# S7_Power.net
KiCad netlist of a schematic drawn in Altium Designer
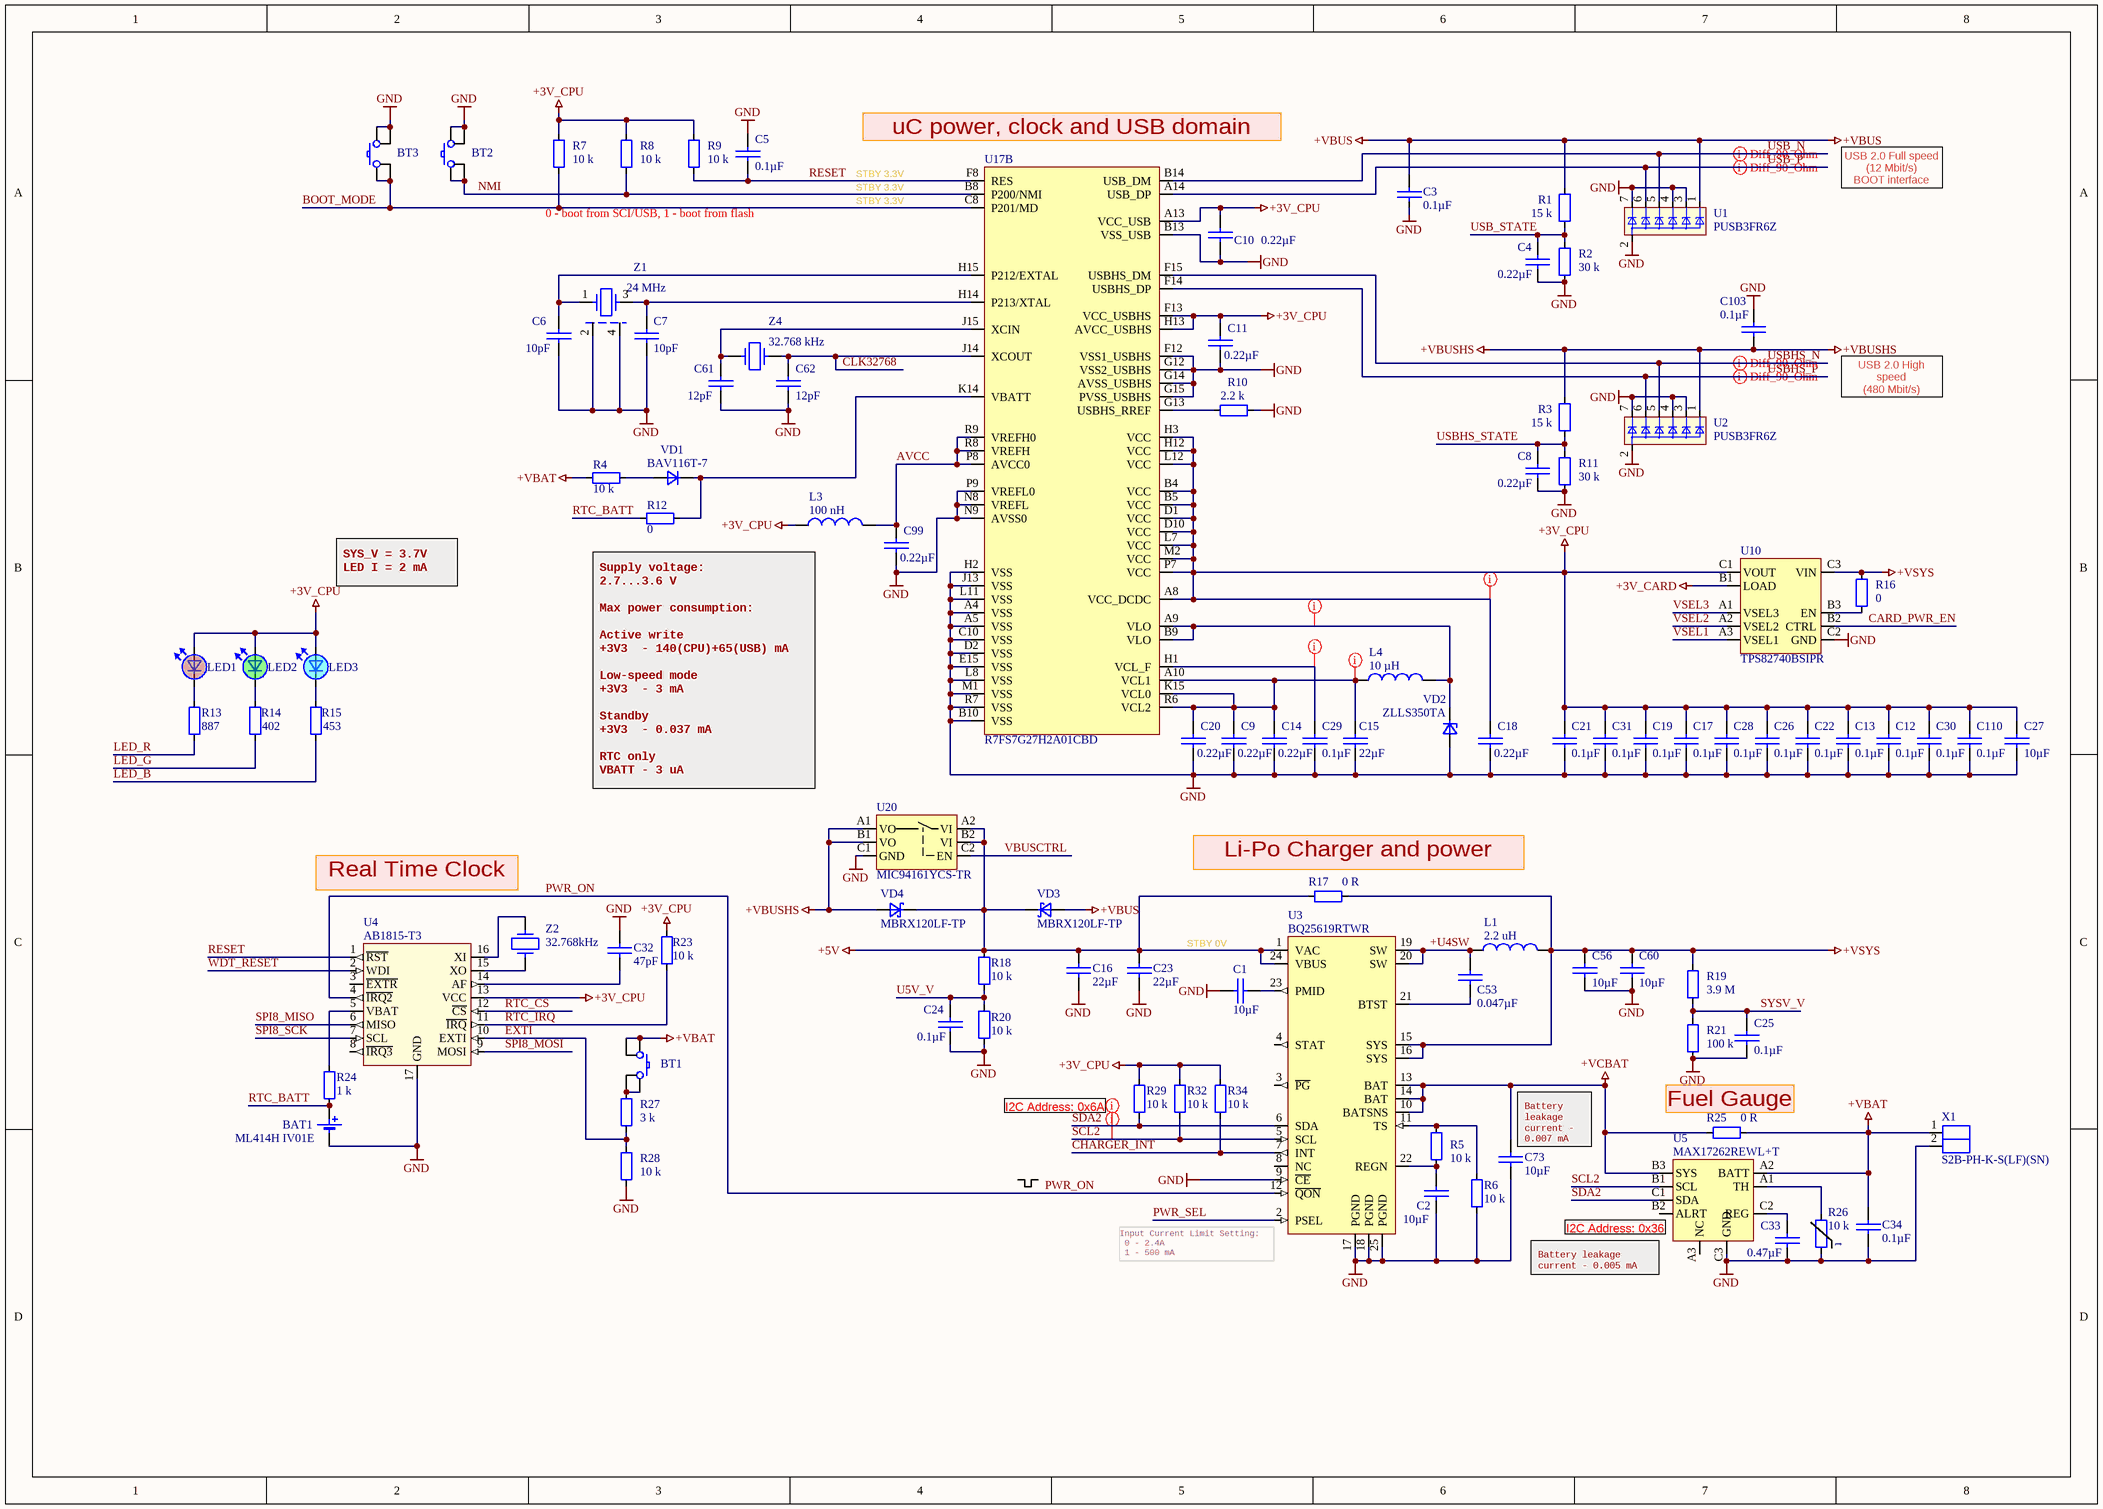
[diagram p0: S7_Power.SchDoc]

(export (version "E")
  (design (tool "Eeschema 10.0.6"))
  (components
    (comp (ref "BAT1")
      (value "ML414H IV01E")
      (footprint "ML414H")
      (description "Coin, 4.8mm 3V Lithium Battery Rechargeable (Secondary) 1mAh")
      (fields (field (name "PARTNUM") "728-1052-1-ND") (field (name "MANUFACTURER") "Seiko Instruments"))
      (libsource (lib "ea_PowerSources") (part "ML414H IV01E"))
    )
    (comp (ref "BT1")
      (value "EVP-AVAA1A")
      (footprint "EVPAV")
      (description "Tactile Switch SPST-NO Side Actuated Edge Mount, Right Angle")
      (fields
        (field (name "MANUFACTURER") "Panasonic Electronic Components")
        (field (name "PARTNUM") "P16849CT-ND")
      )
      (libsource (lib "ea_Buttons") (part "EVP-AVAA1A"))
    )
    (comp (ref "BT2")
      (value "EVP-AVAA1A")
      (footprint "EVPAV")
      (description "Tactile Switch SPST-NO Side Actuated Edge Mount, Right Angle")
      (fields
        (field (name "MANUFACTURER") "Panasonic Electronic Components")
        (field (name "PARTNUM") "P16849CT-ND")
      )
      (libsource (lib "ea_Buttons") (part "EVP-AVAA1A"))
    )
    (comp (ref "BT3")
      (value "EVP-AVAA1A")
      (footprint "EVPAV")
      (description "Tactile Switch SPST-NO Side Actuated Edge Mount, Right Angle")
      (fields
        (field (name "MANUFACTURER") "Panasonic Electronic Components")
        (field (name "PARTNUM") "P16849CT-ND")
      )
      (libsource (lib "ea_Buttons") (part "EVP-AVAA1A"))
    )
    (comp (ref "C1")
      (value "10µF")
      (footprint "0603 CAP")
      (description "10µF, ±10%, 16V, X5R, 0603 (1608 Metric), -55°C ~ 85°C, -, Automotive")
      (fields
        (field (name "PART NUMBER") "GRT188R61C106KE13D")
        (field (name "MANUFACTURER") "Murata Electronics North America")
      )
      (libsource (lib "ea_PassivComps") (part "Capacitor"))
    )
    (comp (ref "C2")
      (value "10µF")
      (footprint "0603 CAP")
      (description "10µF, ±10%, 16V, X5R, 0603 (1608 Metric), -55°C ~ 85°C, -, Automotive")
      (fields
        (field (name "PART NUMBER") "GRT188R61C106KE13D")
        (field (name "MANUFACTURER") "Murata Electronics North America")
      )
      (libsource (lib "ea_PassivComps") (part "Capacitor"))
    )
    (comp (ref "C3")
      (value "0.1µF")
      (footprint "0402 CAP")
      (description "0.1µF, ±10%, 50V, X7R, 0402 (1005 Metric), -55°C ~ 125°C, -, General Purpose")
      (fields
        (field (name "PART NUMBER") "0402B104K500CT")
        (field (name "MANUFACTURER") "Walsin Technology Corporation")
      )
      (libsource (lib "ea_PassivComps") (part "Capacitor"))
    )
    (comp (ref "C4")
      (value "0.22µF")
      (footprint "0402 CAP")
      (description "0.22µF, ±10%, 25V, X5R, 0402 (1005 Metric), -55°C ~ 85°C, -, Automotive")
      (fields
        (field (name "PART NUMBER") "GRT155R61E224KE01D")
        (field (name "MANUFACTURER") "Murata Electronics North America")
      )
      (libsource (lib "ea_PassivComps") (part "Capacitor"))
    )
    (comp (ref "C5")
      (value "0.1µF")
      (footprint "0402 CAP")
      (description "0.1µF, ±10%, 50V, X7R, 0402 (1005 Metric), -55°C ~ 125°C, -, General Purpose")
      (fields
        (field (name "PART NUMBER") "0402B104K500CT")
        (field (name "MANUFACTURER") "Walsin Technology Corporation")
      )
      (libsource (lib "ea_PassivComps") (part "Capacitor"))
    )
    (comp (ref "C6")
      (value "10pF")
      (footprint "0402 CAP")
      (description "10pF, ±1%, 50V, C0G, NP0, 0402 (1005 Metric), -55°C ~ 125°C, -, Automotive")
      (fields
        (field (name "PART NUMBER") "GCM1555C1H100FA16D")
        (field (name "MANUFACTURER") "Murata Electronics North America")
      )
      (libsource (lib "ea_PassivComps") (part "Capacitor"))
    )
    (comp (ref "C7")
      (value "10pF")
      (footprint "0402 CAP")
      (description "10pF, ±1%, 50V, C0G, NP0, 0402 (1005 Metric), -55°C ~ 125°C, -, Automotive")
      (fields
        (field (name "PART NUMBER") "GCM1555C1H100FA16D")
        (field (name "MANUFACTURER") "Murata Electronics North America")
      )
      (libsource (lib "ea_PassivComps") (part "Capacitor"))
    )
    (comp (ref "C8")
      (value "0.22µF")
      (footprint "0402 CAP")
      (description "0.22µF, ±10%, 25V, X5R, 0402 (1005 Metric), -55°C ~ 85°C, -, Automotive")
      (fields
        (field (name "PART NUMBER") "GRT155R61E224KE01D")
        (field (name "MANUFACTURER") "Murata Electronics North America")
      )
      (libsource (lib "ea_PassivComps") (part "Capacitor"))
    )
    (comp (ref "C9")
      (value "0.22µF")
      (footprint "0402 CAP")
      (description "0.22µF, ±10%, 25V, X5R, 0402 (1005 Metric), -55°C ~ 85°C, -, Automotive")
      (fields
        (field (name "PART NUMBER") "GRT155R61E224KE01D")
        (field (name "MANUFACTURER") "Murata Electronics North America")
      )
      (libsource (lib "ea_PassivComps") (part "Capacitor"))
    )
    (comp (ref "C10")
      (value "0.22µF")
      (footprint "0402 CAP")
      (description "0.22µF, ±10%, 25V, X5R, 0402 (1005 Metric), -55°C ~ 85°C, -, Automotive")
      (fields
        (field (name "PART NUMBER") "GRT155R61E224KE01D")
        (field (name "MANUFACTURER") "Murata Electronics North America")
      )
      (libsource (lib "ea_PassivComps") (part "Capacitor"))
    )
    (comp (ref "C11")
      (value "0.22µF")
      (footprint "0402 CAP")
      (description "0.22µF, ±10%, 25V, X5R, 0402 (1005 Metric), -55°C ~ 85°C, -, Automotive")
      (fields
        (field (name "PART NUMBER") "GRT155R61E224KE01D")
        (field (name "MANUFACTURER") "Murata Electronics North America")
      )
      (libsource (lib "ea_PassivComps") (part "Capacitor"))
    )
    (comp (ref "C12")
      (value "0.1µF")
      (footprint "0402 CAP")
      (description "0.1µF, ±10%, 50V, X7R, 0402 (1005 Metric), -55°C ~ 125°C, -, General Purpose")
      (fields
        (field (name "PART NUMBER") "0402B104K500CT")
        (field (name "MANUFACTURER") "Walsin Technology Corporation")
      )
      (libsource (lib "ea_PassivComps") (part "Capacitor"))
    )
    (comp (ref "C13")
      (value "0.1µF")
      (footprint "0402 CAP")
      (description "0.1µF, ±10%, 50V, X7R, 0402 (1005 Metric), -55°C ~ 125°C, -, General Purpose")
      (fields
        (field (name "PART NUMBER") "0402B104K500CT")
        (field (name "MANUFACTURER") "Walsin Technology Corporation")
      )
      (libsource (lib "ea_PassivComps") (part "Capacitor"))
    )
    (comp (ref "C14")
      (value "0.22µF")
      (footprint "0402 CAP")
      (description "0.22µF, ±10%, 25V, X5R, 0402 (1005 Metric), -55°C ~ 85°C, -, Automotive")
      (fields
        (field (name "PART NUMBER") "GRT155R61E224KE01D")
        (field (name "MANUFACTURER") "Murata Electronics North America")
      )
      (libsource (lib "ea_PassivComps") (part "Capacitor"))
    )
    (comp (ref "C15")
      (value "22µF")
      (footprint "0402 CAP")
      (description "22µF, ±20%, 6.3V, X5R, 0402 (1005 Metric), -55°C ~ 85°C, -, General Purpose")
      (fields
        (field (name "PART NUMBER") "CL05A226MQ5N6J8")
        (field (name "MANUFACTURER") "Samsung Electro-Mechanics")
      )
      (libsource (lib "ea_PassivComps") (part "Capacitor"))
    )
    (comp (ref "C16")
      (value "22µF")
      (footprint "0603 CAP")
      (description "22µF, ±20%, 10V, X5R, 0603 (1608 Metric), -55°C ~ 85°C, -, SMPS Filtering")
      (fields (field (name "PART NUMBER") "LMK107BBJ226MA-T") (field (name "MANUFACTURER") "Taiyo Yuden"))
      (libsource (lib "ea_PassivComps") (part "Capacitor"))
    )
    (comp (ref "C17")
      (value "0.1µF")
      (footprint "0402 CAP")
      (description "0.1µF, ±10%, 50V, X7R, 0402 (1005 Metric), -55°C ~ 125°C, -, General Purpose")
      (fields
        (field (name "PART NUMBER") "0402B104K500CT")
        (field (name "MANUFACTURER") "Walsin Technology Corporation")
      )
      (libsource (lib "ea_PassivComps") (part "Capacitor"))
    )
    (comp (ref "C18")
      (value "0.22µF")
      (footprint "0402 CAP")
      (description "0.22µF, ±10%, 25V, X5R, 0402 (1005 Metric), -55°C ~ 85°C, -, Automotive")
      (fields
        (field (name "PART NUMBER") "GRT155R61E224KE01D")
        (field (name "MANUFACTURER") "Murata Electronics North America")
      )
      (libsource (lib "ea_PassivComps") (part "Capacitor"))
    )
    (comp (ref "C19")
      (value "0.1µF")
      (footprint "0402 CAP")
      (description "0.1µF, ±10%, 50V, X7R, 0402 (1005 Metric), -55°C ~ 125°C, -, General Purpose")
      (fields
        (field (name "PART NUMBER") "0402B104K500CT")
        (field (name "MANUFACTURER") "Walsin Technology Corporation")
      )
      (libsource (lib "ea_PassivComps") (part "Capacitor"))
    )
    (comp (ref "C20")
      (value "0.22µF")
      (footprint "0402 CAP")
      (description "0.22µF, ±10%, 25V, X5R, 0402 (1005 Metric), -55°C ~ 85°C, -, Automotive")
      (fields
        (field (name "PART NUMBER") "GRT155R61E224KE01D")
        (field (name "MANUFACTURER") "Murata Electronics North America")
      )
      (libsource (lib "ea_PassivComps") (part "Capacitor"))
    )
    (comp (ref "C21")
      (value "0.1µF")
      (footprint "0402 CAP")
      (description "0.1µF, ±10%, 50V, X7R, 0402 (1005 Metric), -55°C ~ 125°C, -, General Purpose")
      (fields
        (field (name "PART NUMBER") "0402B104K500CT")
        (field (name "MANUFACTURER") "Walsin Technology Corporation")
      )
      (libsource (lib "ea_PassivComps") (part "Capacitor"))
    )
    (comp (ref "C22")
      (value "0.1µF")
      (footprint "0402 CAP")
      (description "0.1µF, ±10%, 50V, X7R, 0402 (1005 Metric), -55°C ~ 125°C, -, General Purpose")
      (fields
        (field (name "PART NUMBER") "0402B104K500CT")
        (field (name "MANUFACTURER") "Walsin Technology Corporation")
      )
      (libsource (lib "ea_PassivComps") (part "Capacitor"))
    )
    (comp (ref "C23")
      (value "22µF")
      (footprint "0603 CAP")
      (description "22µF, ±20%, 10V, X5R, 0603 (1608 Metric), -55°C ~ 85°C, -, SMPS Filtering")
      (fields (field (name "PART NUMBER") "LMK107BBJ226MA-T") (field (name "MANUFACTURER") "Taiyo Yuden"))
      (libsource (lib "ea_PassivComps") (part "Capacitor"))
    )
    (comp (ref "C24")
      (value "0.1µF")
      (footprint "0402 CAP")
      (description "0.1µF, ±10%, 50V, X7R, 0402 (1005 Metric), -55°C ~ 125°C, -, General Purpose")
      (fields
        (field (name "PART NUMBER") "0402B104K500CT")
        (field (name "MANUFACTURER") "Walsin Technology Corporation")
      )
      (libsource (lib "ea_PassivComps") (part "Capacitor"))
    )
    (comp (ref "C25")
      (value "0.1µF")
      (footprint "0402 CAP")
      (description "0.1µF, ±10%, 50V, X7R, 0402 (1005 Metric), -55°C ~ 125°C, -, General Purpose")
      (fields
        (field (name "PART NUMBER") "0402B104K500CT")
        (field (name "MANUFACTURER") "Walsin Technology Corporation")
      )
      (libsource (lib "ea_PassivComps") (part "Capacitor"))
    )
    (comp (ref "C26")
      (value "0.1µF")
      (footprint "0402 CAP")
      (description "0.1µF, ±10%, 50V, X7R, 0402 (1005 Metric), -55°C ~ 125°C, -, General Purpose")
      (fields
        (field (name "PART NUMBER") "0402B104K500CT")
        (field (name "MANUFACTURER") "Walsin Technology Corporation")
      )
      (libsource (lib "ea_PassivComps") (part "Capacitor"))
    )
    (comp (ref "C27")
      (value "10µF")
      (footprint "0603 CAP")
      (description "10µF, ±10%, 16V, X5R, 0603 (1608 Metric), -55°C ~ 85°C, -, Automotive")
      (fields
        (field (name "PART NUMBER") "GRT188R61C106KE13D")
        (field (name "MANUFACTURER") "Murata Electronics North America")
      )
      (libsource (lib "ea_PassivComps") (part "Capacitor"))
    )
    (comp (ref "C28")
      (value "0.1µF")
      (footprint "0402 CAP")
      (description "0.1µF, ±10%, 50V, X7R, 0402 (1005 Metric), -55°C ~ 125°C, -, General Purpose")
      (fields
        (field (name "PART NUMBER") "0402B104K500CT")
        (field (name "MANUFACTURER") "Walsin Technology Corporation")
      )
      (libsource (lib "ea_PassivComps") (part "Capacitor"))
    )
    (comp (ref "C29")
      (value "0.1µF")
      (footprint "0402 CAP")
      (description "0.1µF, ±10%, 50V, X7R, 0402 (1005 Metric), -55°C ~ 125°C, -, General Purpose")
      (fields
        (field (name "PART NUMBER") "0402B104K500CT")
        (field (name "MANUFACTURER") "Walsin Technology Corporation")
      )
      (libsource (lib "ea_PassivComps") (part "Capacitor"))
    )
    (comp (ref "C30")
      (value "0.1µF")
      (footprint "0402 CAP")
      (description "0.1µF, ±10%, 50V, X7R, 0402 (1005 Metric), -55°C ~ 125°C, -, General Purpose")
      (fields
        (field (name "PART NUMBER") "0402B104K500CT")
        (field (name "MANUFACTURER") "Walsin Technology Corporation")
      )
      (libsource (lib "ea_PassivComps") (part "Capacitor"))
    )
    (comp (ref "C31")
      (value "0.1µF")
      (footprint "0402 CAP")
      (description "0.1µF, ±10%, 50V, X7R, 0402 (1005 Metric), -55°C ~ 125°C, -, General Purpose")
      (fields
        (field (name "PART NUMBER") "0402B104K500CT")
        (field (name "MANUFACTURER") "Walsin Technology Corporation")
      )
      (libsource (lib "ea_PassivComps") (part "Capacitor"))
    )
    (comp (ref "C32")
      (value "47pF")
      (footprint "0402 CAP")
      (fields
        (field (name "PART NUMBER") "GJM1555C1H470FB01D")
        (field (name "MANUFACTURER") "Murata Electronics North America")
        (field (name "PARTNUM") "490-16376-1-ND")
      )
      (libsource (lib "ea_PassivComps") (part "Capacitor"))
    )
    (comp (ref "C33")
      (value "0.47µF")
      (footprint "0402 CAP")
      (description "0.47µF, ±20%, 25V, X5R, 0402 (1005 Metric), -55°C ~ 85°C, -, Automotive")
      (fields
        (field (name "PART NUMBER") "GRT155R61E474ME01D")
        (field (name "MANUFACTURER") "Murata Electronics North America")
      )
      (libsource (lib "ea_PassivComps") (part "Capacitor"))
    )
    (comp (ref "C34")
      (value "0.1µF")
      (footprint "0402 CAP")
      (description "0.1µF, ±10%, 50V, X7R, 0402 (1005 Metric), -55°C ~ 125°C, -, General Purpose")
      (fields
        (field (name "PART NUMBER") "0402B104K500CT")
        (field (name "MANUFACTURER") "Walsin Technology Corporation")
      )
      (libsource (lib "ea_PassivComps") (part "Capacitor"))
    )
    (comp (ref "C53")
      (value "0.047µF")
      (footprint "0402 CAP")
      (description "0.047µF, ±10%, 25V, X7R, 0402 (1005 Metric), -55°C ~ 125°C, -, General Purpose")
      (fields (field (name "PART NUMBER") "CC0402KRX7R8BB473") (field (name "MANUFACTURER") "Yageo"))
      (libsource (lib "ea_PassivComps") (part "Capacitor"))
    )
    (comp (ref "C56")
      (value "10µF")
      (footprint "0603 CAP")
      (description "10µF, ±10%, 16V, X5R, 0603 (1608 Metric), -55°C ~ 85°C, -, Automotive")
      (fields
        (field (name "PART NUMBER") "GRT188R61C106KE13D")
        (field (name "MANUFACTURER") "Murata Electronics North America")
      )
      (libsource (lib "ea_PassivComps") (part "Capacitor"))
    )
    (comp (ref "C60")
      (value "10µF")
      (footprint "0603 CAP")
      (description "10µF, ±10%, 16V, X5R, 0603 (1608 Metric), -55°C ~ 85°C, -, Automotive")
      (fields
        (field (name "PART NUMBER") "GRT188R61C106KE13D")
        (field (name "MANUFACTURER") "Murata Electronics North America")
      )
      (libsource (lib "ea_PassivComps") (part "Capacitor"))
    )
    (comp (ref "C61")
      (value "12pF")
      (footprint "0402 CAP")
      (description "12pF, ±2%, 50V, C0G, NP0, 0402 (1005 Metric), -55°C ~ 125°C, -, General Purpose")
      (fields
        (field (name "PART NUMBER") "0402N120G500CT")
        (field (name "MANUFACTURER") "Walsin Technology Corporation")
      )
      (libsource (lib "ea_PassivComps") (part "Capacitor"))
    )
    (comp (ref "C62")
      (value "12pF")
      (footprint "0402 CAP")
      (description "12pF, ±2%, 50V, C0G, NP0, 0402 (1005 Metric), -55°C ~ 125°C, -, General Purpose")
      (fields
        (field (name "PART NUMBER") "0402N120G500CT")
        (field (name "MANUFACTURER") "Walsin Technology Corporation")
      )
      (libsource (lib "ea_PassivComps") (part "Capacitor"))
    )
    (comp (ref "C73")
      (value "10µF")
      (footprint "0603 CAP")
      (description "10µF, ±10%, 16V, X5R, 0603 (1608 Metric), -55°C ~ 85°C, -, Automotive")
      (fields
        (field (name "PART NUMBER") "GRT188R61C106KE13D")
        (field (name "MANUFACTURER") "Murata Electronics North America")
      )
      (libsource (lib "ea_PassivComps") (part "Capacitor"))
    )
    (comp (ref "C99")
      (value "0.22µF")
      (footprint "0402 CAP")
      (description "0.22µF, ±10%, 25V, X5R, 0402 (1005 Metric), -55°C ~ 85°C, -, Automotive")
      (fields
        (field (name "PART NUMBER") "GRT155R61E224KE01D")
        (field (name "MANUFACTURER") "Murata Electronics North America")
      )
      (libsource (lib "ea_PassivComps") (part "Capacitor"))
    )
    (comp (ref "C103")
      (value "0.1µF")
      (footprint "0402 CAP")
      (description "0.1µF, ±10%, 50V, X7R, 0402 (1005 Metric), -55°C ~ 125°C, -, General Purpose")
      (fields
        (field (name "PART NUMBER") "0402B104K500CT")
        (field (name "MANUFACTURER") "Walsin Technology Corporation")
      )
      (libsource (lib "ea_PassivComps") (part "Capacitor"))
    )
    (comp (ref "C110")
      (value "0.1µF")
      (footprint "0402 CAP")
      (description "0.1µF, ±10%, 50V, X7R, 0402 (1005 Metric), -55°C ~ 125°C, -, General Purpose")
      (fields
        (field (name "PART NUMBER") "0402B104K500CT")
        (field (name "MANUFACTURER") "Walsin Technology Corporation")
      )
      (libsource (lib "ea_PassivComps") (part "Capacitor"))
    )
    (comp (ref "L1")
      (value "2.2 uH")
      (footprint "IHLP-2020BZ-11")
      (description "2.2 uH, 4.2 A, 50 mOhms, +-20%,-55.. +125 C")
      (fields (field (name "MANUFACTURER") "Vishay Dale") (field (name "PARTNUM") "541-1088-1-ND"))
      (libsource (lib "ea_Inductors") (part "IHLP2020BZER2R2M01"))
    )
    (comp (ref "L3")
      (value "100 nH")
      (footprint "INDC1005-0402")
      (description "100nH, ±5%, 200 мА, 2 Ohm, 0402, -55..+125 C")
      (fields (field (name "MANUFACTURER") "TDK Corporation") (field (name "TOLERANCE") "±5%"))
      (libsource (lib "ea_Inductors") (part "MLG1005SR10JT000"))
    )
    (comp (ref "L4")
      (value "10 µH")
      (footprint "SRU3017")
      (description "10µH Shielded Wirewound Inductor 850mA 120mOhm Nonstandard, -40...+125 C")
      (fields (field (name "MANUFACTURER") "Bourns Inc.") (field (name "PARTNUM") "SRU3017-100YCT-ND"))
      (libsource (lib "ea_Inductors") (part "SRU3017-100Y"))
    )
    (comp (ref "LED1")
      (value "APHHS1005LSECK/J3-PF")
      (footprint "2-SMD RED")
      (description "Red 625nm LED Indication - Discrete 1.8V, 2 mA,  0402 (1005 Metric)")
      (fields (field (name "MANUFACTURER") "Kingbright") (field (name "PARTNUM") "754-2123-1-ND"))
      (libsource (lib "ea_Indicators") (part "APHHS1005LSECK/J3-PF"))
    )
    (comp (ref "LED2")
      (value "APHHS1005LZGCK-V")
      (footprint "2-SMD GREEN")
      (description "Green 525nm LED Indication - Discrete 2.65V, 2mA, 0402 (1005 Metric)")
      (fields (field (name "MANUFACTURER") "Kingbright") (field (name "PARTNUM") "754-2126-1-ND"))
      (libsource (lib "ea_Indicators") (part "APHHS1005LZGCK-V"))
    )
    (comp (ref "LED3")
      (value "APHHS1005LQBC/D-V")
      (footprint "2-SMD BLUE")
      (description "Blue 465nm LED Indication - Discrete 2.2V, 2mA, 0402 (1005 Metric)")
      (fields (field (name "MANUFACTURER") "Kingbright") (field (name "PARTNUM") "754-2122-1-ND"))
      (libsource (lib "ea_Indicators") (part "APHHS1005LQBC/D-V"))
    )
    (comp (ref "R1")
      (value "15 k")
      (footprint "0402")
      (fields
        (field (name "MANUFACTURER") "Stackpole Electronics Inc")
        (field (name "TOLERANCE") "±1%")
        (field (name "VOLTAGE") "75V")
      )
      (libsource (lib "") (part "Resistor_1"))
    )
    (comp (ref "R2")
      (value "30 k")
      (footprint "0402")
      (fields
        (field (name "MANUFACTURER") "Stackpole Electronics Inc")
        (field (name "TOLERANCE") "±1%")
        (field (name "VOLTAGE") "75V")
      )
      (libsource (lib "") (part "Resistor_1"))
    )
    (comp (ref "R3")
      (value "15 k")
      (footprint "0402")
      (fields
        (field (name "MANUFACTURER") "Stackpole Electronics Inc")
        (field (name "TOLERANCE") "±1%")
        (field (name "VOLTAGE") "75V")
      )
      (libsource (lib "") (part "Resistor_1"))
    )
    (comp (ref "R4")
      (value "10 k")
      (footprint "0402")
      (fields
        (field (name "MANUFACTURER") "Stackpole Electronics Inc")
        (field (name "TOLERANCE") "±1%")
        (field (name "VOLTAGE") "75V")
      )
      (libsource (lib "") (part "Resistor_1"))
    )
    (comp (ref "R5")
      (value "10 k")
      (footprint "0402")
      (fields
        (field (name "MANUFACTURER") "Stackpole Electronics Inc")
        (field (name "TOLERANCE") "±1%")
        (field (name "VOLTAGE") "75V")
      )
      (libsource (lib "") (part "Resistor_2"))
    )
    (comp (ref "R6")
      (value "10 k")
      (footprint "0402")
      (fields
        (field (name "MANUFACTURER") "Stackpole Electronics Inc")
        (field (name "TOLERANCE") "±1%")
        (field (name "VOLTAGE") "75V")
      )
      (libsource (lib "ea_PassivComps") (part "Resistor"))
    )
    (comp (ref "R7")
      (value "10 k")
      (footprint "0402")
      (fields
        (field (name "MANUFACTURER") "Stackpole Electronics Inc")
        (field (name "TOLERANCE") "±1%")
        (field (name "VOLTAGE") "75V")
      )
      (libsource (lib "ea_PassivComps") (part "Resistor"))
    )
    (comp (ref "R8")
      (value "10 k")
      (footprint "0402")
      (fields
        (field (name "MANUFACTURER") "Stackpole Electronics Inc")
        (field (name "TOLERANCE") "±1%")
        (field (name "VOLTAGE") "75V")
      )
      (libsource (lib "ea_PassivComps") (part "Resistor"))
    )
    (comp (ref "R9")
      (value "10 k")
      (footprint "0402")
      (fields
        (field (name "MANUFACTURER") "Stackpole Electronics Inc")
        (field (name "TOLERANCE") "±1%")
        (field (name "VOLTAGE") "75V")
      )
      (libsource (lib "ea_PassivComps") (part "Resistor"))
    )
    (comp (ref "R10")
      (value "2.2 k")
      (footprint "0402")
      (fields
        (field (name "MANUFACTURER") "Stackpole Electronics Inc")
        (field (name "TOLERANCE") "±1%")
        (field (name "VOLTAGE") "75V")
      )
      (libsource (lib "") (part "Resistor_3"))
    )
    (comp (ref "R11")
      (value "30 k")
      (footprint "0402")
      (fields
        (field (name "MANUFACTURER") "Stackpole Electronics Inc")
        (field (name "TOLERANCE") "±1%")
        (field (name "VOLTAGE") "75V")
      )
      (libsource (lib "") (part "Resistor_1"))
    )
    (comp (ref "R12")
      (value "0")
      (footprint "0402")
      (description "0 Ohms Jumper 0.063W, 1/16W Chip Resistor 0402 (1005 Metric) Thick Film")
      (fields (field (name "MANUFACTURER") "Walsin Technology Corporation") (field (name "VOLTAGE") "50 V"))
      (libsource (lib "ea_Resistors_0402") (part "WR04X000 PTL"))
    )
    (comp (ref "R13")
      (value "887")
      (footprint "0402")
      (fields
        (field (name "MANUFACTURER") "Stackpole Electronics Inc")
        (field (name "TOLERANCE") "±1%")
        (field (name "VOLTAGE") "75V")
      )
      (libsource (lib "ea_PassivComps") (part "Resistor"))
    )
    (comp (ref "R14")
      (value "402")
      (footprint "0402")
      (fields
        (field (name "MANUFACTURER") "Stackpole Electronics Inc")
        (field (name "TOLERANCE") "±1%")
        (field (name "VOLTAGE") "75V")
      )
      (libsource (lib "ea_PassivComps") (part "Resistor"))
    )
    (comp (ref "R15")
      (value "453")
      (footprint "0402")
      (fields
        (field (name "MANUFACTURER") "Stackpole Electronics Inc")
        (field (name "TOLERANCE") "±1%")
        (field (name "VOLTAGE") "75V")
      )
      (libsource (lib "ea_PassivComps") (part "Resistor"))
    )
    (comp (ref "R16")
      (value "0")
      (footprint "0402")
      (description "0 Ohms Jumper 0.063W, 1/16W Chip Resistor 0402 (1005 Metric) Thick Film")
      (fields (field (name "MANUFACTURER") "Walsin Technology Corporation") (field (name "VOLTAGE") "50 V"))
      (libsource (lib "") (part "WR04X000 PTL_1"))
    )
    (comp (ref "R17")
      (value "0 R")
      (footprint "0603")
      (fields
        (field (name "MANUFACTURER") "KOA Speer Electronics, Inc.")
        (field (name "PARTNUM") "2019-RK73Z1JTTDCT-ND")
        (field (name "Comment") "RK73Z1JTTD")
      )
      (libsource (lib "ea_Resistors_0603") (part "RK73Z1JTTD"))
    )
    (comp (ref "R18")
      (value "10 k")
      (footprint "0402")
      (fields
        (field (name "MANUFACTURER") "Stackpole Electronics Inc")
        (field (name "TOLERANCE") "±1%")
        (field (name "VOLTAGE") "75V")
      )
      (libsource (lib "") (part "Resistor_1"))
    )
    (comp (ref "R19")
      (value "3.9 M")
      (footprint "0402")
      (fields
        (field (name "MANUFACTURER") "Vishay Dale")
        (field (name "TOLERANCE") "±1%")
        (field (name "VOLTAGE") "75V")
      )
      (libsource (lib "") (part "Resistor_2"))
    )
    (comp (ref "R20")
      (value "10 k")
      (footprint "0402")
      (fields
        (field (name "MANUFACTURER") "Stackpole Electronics Inc")
        (field (name "TOLERANCE") "±1%")
        (field (name "VOLTAGE") "75V")
      )
      (libsource (lib "") (part "Resistor_1"))
    )
    (comp (ref "R21")
      (value "100 k")
      (footprint "0402")
      (fields
        (field (name "MANUFACTURER") "Yageo")
        (field (name "TOLERANCE") "±1%")
        (field (name "VOLTAGE") "75V")
      )
      (libsource (lib "") (part "Resistor_2"))
    )
    (comp (ref "R23")
      (value "10 k")
      (footprint "0402")
      (fields
        (field (name "MANUFACTURER") "Stackpole Electronics Inc")
        (field (name "TOLERANCE") "±1%")
        (field (name "VOLTAGE") "75V")
      )
      (libsource (lib "") (part "Resistor_2"))
    )
    (comp (ref "R24")
      (value "1 k")
      (footprint "0402")
      (fields
        (field (name "MANUFACTURER") "Yageo")
        (field (name "TOLERANCE") "±1%")
        (field (name "VOLTAGE") "75V")
      )
      (libsource (lib "ea_PassivComps") (part "Resistor"))
    )
    (comp (ref "R25")
      (value "0 R")
      (footprint "0603")
      (description "0 Ohms Jumper 0.1W, 1/10W Chip Resistor 0603 (1608 Metric) - Thick Film")
      (fields (field (name "MANUFACTURER") "Venkel") (field (name "VOLTAGE") "75 V"))
      (libsource (lib "ea_Resistors_0603") (part "CR0603-10W-000T"))
    )
    (comp (ref "R26")
      (value "10 k")
      (footprint "0402")
      (description "NTC Thermistor 10k , B25/85=3435K,  -40°C ~ 125°C")
      (fields (field (name "MANUFACTURER") "TDK Corporation") (field (name "TOLERANCE") "±0.5%"))
      (libsource (lib "ea_Resistors_0402") (part "NTCG103JX103DTDS"))
    )
    (comp (ref "R27")
      (value "3 k")
      (footprint "0402")
      (fields
        (field (name "MANUFACTURER") "Yageo")
        (field (name "TOLERANCE") "±1%")
        (field (name "VOLTAGE") "75V")
      )
      (libsource (lib "ea_PassivComps") (part "Resistor"))
    )
    (comp (ref "R28")
      (value "10 k")
      (footprint "0402")
      (fields
        (field (name "MANUFACTURER") "Stackpole Electronics Inc")
        (field (name "TOLERANCE") "±1%")
        (field (name "VOLTAGE") "75V")
      )
      (libsource (lib "ea_PassivComps") (part "Resistor"))
    )
    (comp (ref "R29")
      (value "10 k")
      (footprint "0402")
      (fields
        (field (name "MANUFACTURER") "Stackpole Electronics Inc")
        (field (name "TOLERANCE") "±1%")
        (field (name "VOLTAGE") "75V")
      )
      (libsource (lib "ea_PassivComps") (part "Resistor"))
    )
    (comp (ref "R32")
      (value "10 k")
      (footprint "0402")
      (fields
        (field (name "MANUFACTURER") "Stackpole Electronics Inc")
        (field (name "TOLERANCE") "±1%")
        (field (name "VOLTAGE") "75V")
      )
      (libsource (lib "ea_PassivComps") (part "Resistor"))
    )
    (comp (ref "R34")
      (value "10 k")
      (footprint "0402")
      (fields
        (field (name "MANUFACTURER") "Stackpole Electronics Inc")
        (field (name "TOLERANCE") "±1%")
        (field (name "VOLTAGE") "75V")
      )
      (libsource (lib "ea_PassivComps") (part "Resistor"))
    )
    (comp (ref "U1")
      (value "PUSB3FR6Z")
      (footprint "SOT1358-1")
      (description "TVS Diode, 3V (Typ) Clamp 5A (8/20µs) Ipp ,  7-XSON (1.1x2.1), -40°C ~ 85°C (TA)")
      (fields (field (name "MANUFACTURER") "Nexperia USA Inc.") (field (name "PARTNUM") "1727-2027-1-ND"))
      (libsource (lib "ea_TVS_protection") (part "PUSB3FR6Z"))
    )
    (comp (ref "U2")
      (value "PUSB3FR6Z")
      (footprint "SOT1358-1")
      (description "TVS Diode, 3V (Typ) Clamp 5A (8/20µs) Ipp ,  7-XSON (1.1x2.1), -40°C ~ 85°C (TA)")
      (fields (field (name "MANUFACTURER") "Nexperia USA Inc.") (field (name "PARTNUM") "1727-2027-1-ND"))
      (libsource (lib "ea_TVS_protection") (part "PUSB3FR6Z"))
    )
    (comp (ref "U3")
      (value "BQ25619RTWR")
      (footprint "TI S-PVQFN-N24")
      (description "Charger IC Lithium Ion/Polymer 24-WQFN (4x4), -40...+85 C")
      (fields
        (field (name "PARTNUM") "296-BQ25619RTWRCT-ND")
        (field (name "MANUFACTURER") "Texas Instruments")
      )
      (libsource (lib "BQ25619") (part "BQ25619RTWR"))
    )
    (comp (ref "U4")
      (value "AB1815-T3")
      (footprint "QFN-16 3x3mm AB18XX")
      (description "Real Time Clock (RTC) IC Clock/Calendar 256B SPI, 16-VFQFN Exposed Pad, -40...+85 C")
      (fields (field (name "MANUFACTURER") "Abracon LLC") (field (name "PARTNUM") "535-11936-1-ND"))
      (libsource (lib "ea_IC_RTC") (part "AB1815-T3"))
    )
    (comp (ref "U5")
      (value "MAX17262REWL+T")
      (footprint "9-WFBGA")
      (description "Battery Fuel Gauge IC LiFePO4/Li-ion 9-WLP, -40°C ~ 85°C (TA)")
      (fields
        (field (name "MANUFACTURER") "Analog Devices Inc./Maxim Integrated")
        (field (name "PARTNUM") "175-MAX17262REWL+TCT-ND")
      )
      (libsource (lib "ea_IC_Chargers_Fuel_Gauges") (part "MAX17262REWL+T"))
    )
    (comp (ref "U10")
      (value "TPS82740BSIPR")
      (footprint "MicroSiP")
      (fields (field (name "MANUFACTURER") "Texas Instruments") (field (name "PARTNUM") "296-46481-1-ND"))
      (libsource (lib "ea_IC_Power_Reg_Ref_Sw") (part "TPS82740BSIPR"))
    )
    (comp (ref "U17")
      (value "R7FS7G27H2A01CBD")
      (footprint "RENESAS_FBGA224")
      (fields (field (name "MANUFACTURER") "Renesas") (field (name "PARTNUM") "R7FS7G27H2A01CBD#AC0-ND"))
      (libsource (lib "ea_IC_CPU") (part "R7FS7G27H2A01CBD#AC0"))
    )
    (comp (ref "U20")
      (value "MIC94161YCS-TR")
      (footprint "6-BALL WLCSP 1.5x1.0")
      (description "Power Switch/Driver 1:1 P-Channel 3A, 14.5mOhm,  6-WLCSP (1x1.5), -40°C ~ 125°C (TJ)")
      (fields (field (name "MANUFACTURER") "Microchip Technology") (field (name "PARTNUM") "576-4453-1-ND"))
      (libsource (lib "ea_IC_load_switches") (part "MIC94161YCS-TR"))
    )
    (comp (ref "VD1")
      (value "BAV116T-7")
      (footprint "SOD523")
      (description "Diode Standard 85V 100mA, 5nA @ 75V, SOD-523, -65°C ~ 150°C")
      (fields (field (name "MANUFACTURER") "Diodes Incorporated") (field (name "PARTNUM") "BAV116T-7DICT-ND"))
      (libsource (lib "ea_Diodes") (part "BAV116T-7"))
    )
    (comp (ref "VD2")
      (value "ZLLS350TA")
      (footprint "SOD523")
      (description "Diode Schottky 40V 380mA (DC) , Fast Recovery, SOD-523")
      (fields (field (name "MANUFACTURER") "Diodes Incorporated") (field (name "PARTNUM") "ZLLS350TACT-ND"))
      (libsource (lib "ea_Diodes") (part "ZLLS350TA"))
    )
    (comp (ref "VD3")
      (value "MBRX120LF-TP")
      (footprint "SOD-123")
      (description "Diode Schottky 20 V 1A, 360 mV @ 1 A ,  Surface Mount SOD-123, -65°C ~ 125°C")
      (fields
        (field (name "MANUFACTURER") "Micro Commercial Co")
        (field (name "PARTNUM") "MBRX120LF-TPMSCT-ND")
      )
      (libsource (lib "ea_Diodes") (part "MBRX120LF-TP"))
    )
    (comp (ref "VD4")
      (value "MBRX120LF-TP")
      (footprint "SOD-123")
      (description "Diode Schottky 20 V 1A, 360 mV @ 1 A ,  Surface Mount SOD-123, -65°C ~ 125°C")
      (fields
        (field (name "MANUFACTURER") "Micro Commercial Co")
        (field (name "PARTNUM") "MBRX120LF-TPMSCT-ND")
      )
      (libsource (lib "ea_Diodes") (part "MBRX120LF-TP"))
    )
    (comp (ref "X1")
      (value "S2B-PH-K-S(LF)(SN)")
      (footprint "S2B-PH-K-S")
      (description "Connector Header Through Hole, Right Angle 2 position 0.079\" (2.00mm)")
      (fields (field (name "MANUFACTURER") "JST Sales America Inc.") (field (name "PARTNUM") "455-1719-ND"))
      (libsource (lib "ea_Connectors_2.0_mm_pitch") (part "S2B-PH-K-S(LF)(SN)"))
    )
    (comp (ref "Z1")
      (value "24 MHz")
      (footprint "4-SMD 2.00mm x 1.60mm")
      (description "24 MHz, 10 pF, ±20ppm, 2.00mm x 1.60mm, -40°C ~ 85°C")
      (fields (field (name "MANUFACTURER") "Abracon LLC") (field (name "PARTNUM") "535-10940-1-ND"))
      (libsource (lib "ea_OSC_CLK_GEN") (part "ABM11-24.000MHZ-D2X-T3"))
    )
    (comp (ref "Z2")
      (value "32.768kHz")
      (footprint "ABS7")
      (description "32.768 kHz ±20ppm Crystal 4pF 70 kOhms 3-SMD, No Lead, 3.20mm x 1.50mm, -40°C ~ 85°C")
      (fields
        (field (name "MANUFACTURER") "Citizen Finedevice Co Ltd")
        (field (name "PARTNUM") "300-8868-1-ND")
      )
      (libsource (lib "ea_OSC_CLK_GEN") (part "CM315E32768DZZT-4PF"))
    )
    (comp (ref "Z4")
      (value "32.768 kHz")
      (footprint "ABS7")
      (description "32.768 kHz, 12.5 pF, 70 kOhm, ±20ppm, 3.2 x 1.5 mm, -40°C ~ 85°C")
      (fields (field (name "MANUFACTURER") "Abracon Corporation") (field (name "PARTNUM") "535-9542-1-ND"))
      (libsource (lib "ea_OSC_CLK_GEN") (part "ABS07-32.768KHZ-T"))
    )
  )
  (nets
    (net (code "1") (name "+3V_CARD") (class "Default")
      (node (ref "U10") (pin "B1") (pinfunction "LOAD_B1") (pintype "passive"))
    )
    (net (code "2") (name "+3V_CPU") (class "Default")
      (node (ref "C10") (pin "1") (pinfunction "1_1") (pintype "passive"))
      (node (ref "C11") (pin "1") (pinfunction "1_1") (pintype "passive"))
      (node (ref "C110") (pin "1") (pinfunction "1_1") (pintype "passive"))
      (node (ref "C12") (pin "1") (pinfunction "1_1") (pintype "passive"))
      (node (ref "C13") (pin "1") (pinfunction "1_1") (pintype "passive"))
      (node (ref "C17") (pin "1") (pinfunction "1_1") (pintype "passive"))
      (node (ref "C18") (pin "1") (pinfunction "1_1") (pintype "passive"))
      (node (ref "C19") (pin "1") (pinfunction "1_1") (pintype "passive"))
      (node (ref "C21") (pin "1") (pinfunction "1_1") (pintype "passive"))
      (node (ref "C22") (pin "1") (pinfunction "1_1") (pintype "passive"))
      (node (ref "C26") (pin "1") (pinfunction "1_1") (pintype "passive"))
      (node (ref "C27") (pin "1") (pinfunction "1_1") (pintype "passive"))
      (node (ref "C28") (pin "1") (pinfunction "1_1") (pintype "passive"))
      (node (ref "C30") (pin "1") (pinfunction "1_1") (pintype "passive"))
      (node (ref "C31") (pin "1") (pinfunction "1_1") (pintype "passive"))
      (node (ref "L3") (pin "1") (pinfunction "1_1") (pintype "passive"))
      (node (ref "LED1") (pin "2") (pinfunction "2_2") (pintype "passive"))
      (node (ref "LED2") (pin "2") (pinfunction "2_2") (pintype "passive"))
      (node (ref "LED3") (pin "2") (pinfunction "2_2") (pintype "passive"))
      (node (ref "R23") (pin "1") (pinfunction "1_1") (pintype "passive"))
      (node (ref "R29") (pin "2") (pinfunction "2_2") (pintype "passive"))
      (node (ref "R32") (pin "2") (pinfunction "2_2") (pintype "passive"))
      (node (ref "R34") (pin "2") (pinfunction "2_2") (pintype "passive"))
      (node (ref "R7") (pin "2") (pinfunction "2_2") (pintype "passive"))
      (node (ref "R8") (pin "2") (pinfunction "2_2") (pintype "passive"))
      (node (ref "R9") (pin "2") (pinfunction "2_2") (pintype "passive"))
      (node (ref "U10") (pin "C1") (pinfunction "VOUT_C1") (pintype "passive"))
      (node (ref "U17") (pin "A13") (pinfunction "VCC_USB_A13") (pintype "power_in"))
      (node (ref "U17") (pin "A8") (pinfunction "VCC_DCDC_A8") (pintype "power_in"))
      (node (ref "U17") (pin "B4") (pinfunction "VCC_B4") (pintype "power_in"))
      (node (ref "U17") (pin "B5") (pinfunction "VCC_B5") (pintype "power_in"))
      (node (ref "U17") (pin "D1") (pinfunction "VCC_D1") (pintype "power_in"))
      (node (ref "U17") (pin "D10") (pinfunction "VCC_D10") (pintype "power_in"))
      (node (ref "U17") (pin "F13") (pinfunction "VCC_USBHS_F13") (pintype "power_in"))
      (node (ref "U17") (pin "H12") (pinfunction "VCC_H12") (pintype "power_in"))
      (node (ref "U17") (pin "H13") (pinfunction "AVCC_USBHS_H13") (pintype "power_in"))
      (node (ref "U17") (pin "H3") (pinfunction "VCC_H3") (pintype "power_in"))
      (node (ref "U17") (pin "L12") (pinfunction "VCC_L12") (pintype "power_in"))
      (node (ref "U17") (pin "L7") (pinfunction "VCC_L7") (pintype "power_in"))
      (node (ref "U17") (pin "M2") (pinfunction "VCC_M2") (pintype "power_in"))
      (node (ref "U17") (pin "P7") (pinfunction "VCC_P7") (pintype "power_in"))
      (node (ref "U4") (pin "13") (pinfunction "VCC_13") (pintype "passive"))
    )
    (net (code "3") (name "+5V") (class "Default")
      (node (ref "C16") (pin "1") (pinfunction "1_1") (pintype "passive"))
      (node (ref "C23") (pin "1") (pinfunction "1_1") (pintype "passive"))
      (node (ref "R17") (pin "1") (pinfunction "1_1") (pintype "passive"))
      (node (ref "R18") (pin "1") (pinfunction "1_1") (pintype "passive"))
      (node (ref "U20") (pin "A2") (pinfunction "VI_A2") (pintype "passive"))
      (node (ref "U20") (pin "B2") (pinfunction "VI_B2") (pintype "passive"))
      (node (ref "U3") (pin "1") (pinfunction "VAC_1") (pintype "power_in"))
      (node (ref "U3") (pin "24") (pinfunction "VBUS_24") (pintype "power_in"))
      (node (ref "VD3") (pin "1") (pinfunction "C_1") (pintype "passive"))
      (node (ref "VD4") (pin "1") (pinfunction "C_1") (pintype "passive"))
    )
    (net (code "4") (name "+VBAT") (class "Default")
      (node (ref "BT1") (pin "1") (pinfunction "1_1") (pintype "passive"))
      (node (ref "BT1") (pin "2") (pinfunction "2_2") (pintype "passive"))
      (node (ref "C34") (pin "2") (pinfunction "2_2") (pintype "passive"))
      (node (ref "R25") (pin "2") (pinfunction "2_2") (pintype "passive"))
      (node (ref "R4") (pin "2") (pinfunction "2_2") (pintype "passive"))
      (node (ref "U5") (pin "A2") (pinfunction "BATT_A2") (pintype "passive"))
      (node (ref "X1") (pin "1") (pinfunction "1_1") (pintype "passive"))
    )
    (net (code "5") (name "+VBUS") (class "Default")
      (node (ref "C3") (pin "2") (pinfunction "2_2") (pintype "passive"))
      (node (ref "R1") (pin "1") (pinfunction "1_1") (pintype "passive"))
      (node (ref "U1") (pin "1") (pinfunction "1_1") (pintype "passive"))
      (node (ref "VD3") (pin "2") (pinfunction "A_2") (pintype "passive"))
    )
    (net (code "6") (name "+VBUSHS") (class "Default")
      (node (ref "C103") (pin "2") (pinfunction "2_2") (pintype "passive"))
      (node (ref "R3") (pin "1") (pinfunction "1_1") (pintype "passive"))
      (node (ref "U2") (pin "1") (pinfunction "1_1") (pintype "passive"))
      (node (ref "U20") (pin "A1") (pinfunction "VO_A1") (pintype "passive"))
      (node (ref "U20") (pin "B1") (pinfunction "VO_B1") (pintype "passive"))
      (node (ref "VD4") (pin "2") (pinfunction "A_2") (pintype "passive"))
    )
    (net (code "7") (name "+VCBAT") (class "Default")
      (node (ref "C73") (pin "2") (pinfunction "2_2") (pintype "passive"))
      (node (ref "R25") (pin "1") (pinfunction "1_1") (pintype "passive"))
      (node (ref "U3") (pin "10") (pinfunction "BATSNS_10") (pintype "passive"))
      (node (ref "U3") (pin "13") (pinfunction "BAT_13") (pintype "power_in"))
      (node (ref "U3") (pin "14") (pinfunction "BAT_14") (pintype "power_in"))
      (node (ref "U5") (pin "B3") (pinfunction "SYS_B3") (pintype "passive"))
    )
    (net (code "8") (name "+VSYS") (class "Default")
      (node (ref "C56") (pin "1") (pinfunction "1_1") (pintype "passive"))
      (node (ref "C60") (pin "1") (pinfunction "1_1") (pintype "passive"))
      (node (ref "L1") (pin "2") (pinfunction "2_2") (pintype "passive"))
      (node (ref "R16") (pin "2") (pinfunction "2_2") (pintype "passive"))
      (node (ref "R17") (pin "2") (pinfunction "2_2") (pintype "passive"))
      (node (ref "R19") (pin "1") (pinfunction "1_1") (pintype "passive"))
      (node (ref "U10") (pin "C3") (pinfunction "VIN_C3") (pintype "passive"))
      (node (ref "U3") (pin "15") (pinfunction "SYS_15") (pintype "power_in"))
      (node (ref "U3") (pin "16") (pinfunction "SYS_16") (pintype "power_in"))
    )
    (net (code "9") (name "/+U4SW") (class "Default")
      (node (ref "C53") (pin "1") (pinfunction "1_1") (pintype "passive"))
      (node (ref "L1") (pin "1") (pinfunction "1_1") (pintype "passive"))
      (node (ref "U3") (pin "19") (pinfunction "SW_19") (pintype "power_in"))
      (node (ref "U3") (pin "20") (pinfunction "SW_20") (pintype "power_in"))
    )
    (net (code "10") (name "/AVCC") (class "Default")
      (node (ref "C99") (pin "1") (pinfunction "1_1") (pintype "passive"))
      (node (ref "L3") (pin "2") (pinfunction "2_2") (pintype "passive"))
      (node (ref "U17") (pin "P8") (pinfunction "AVCC0_P8") (pintype "power_in"))
      (node (ref "U17") (pin "R8") (pinfunction "VREFH_R8") (pintype "power_in"))
      (node (ref "U17") (pin "R9") (pinfunction "VREFH0_R9") (pintype "power_in"))
    )
    (net (code "11") (name "/BOOT_MODE") (class "Default")
      (node (ref "BT3") (pin "1") (pinfunction "1_1") (pintype "passive"))
      (node (ref "BT3") (pin "2") (pinfunction "2_2") (pintype "passive"))
      (node (ref "R7") (pin "1") (pinfunction "1_1") (pintype "passive"))
      (node (ref "U17") (pin "C8") (pinfunction "P201/MD_C8") (pintype "bidirectional"))
    )
    (net (code "12") (name "/CARD_PWR_EN") (class "Default")
      (node (ref "U10") (pin "B2") (pinfunction "CTRL_B2") (pintype "passive"))
    )
    (net (code "13") (name "/CHARGER_INT") (class "Default")
      (node (ref "R34") (pin "1") (pinfunction "1_1") (pintype "passive"))
      (node (ref "U3") (pin "7") (pinfunction "INT_7") (pintype "output"))
    )
    (net (code "14") (name "/CLK32768") (class "Default")
      (node (ref "C62") (pin "1") (pinfunction "1_1") (pintype "passive"))
      (node (ref "U17") (pin "J14") (pinfunction "XCOUT_J14") (pintype "bidirectional"))
      (node (ref "Z4") (pin "2") (pinfunction "2_2") (pintype "passive"))
    )
    (net (code "15") (name "/EXTI") (class "Default")
      (node (ref "R27") (pin "1") (pinfunction "1_1") (pintype "passive"))
      (node (ref "R28") (pin "2") (pinfunction "2_2") (pintype "passive"))
      (node (ref "U4") (pin "10") (pinfunction "EXTI_10") (pintype "input"))
    )
    (net (code "16") (name "/LED_B") (class "Default")
      (node (ref "R15") (pin "1") (pinfunction "1_1") (pintype "passive"))
    )
    (net (code "17") (name "/LED_G") (class "Default")
      (node (ref "R14") (pin "1") (pinfunction "1_1") (pintype "passive"))
    )
    (net (code "18") (name "/LED_R") (class "Default")
      (node (ref "R13") (pin "1") (pinfunction "1_1") (pintype "passive"))
    )
    (net (code "19") (name "/NMI") (class "Default")
      (node (ref "BT2") (pin "1") (pinfunction "1_1") (pintype "passive"))
      (node (ref "BT2") (pin "2") (pinfunction "2_2") (pintype "passive"))
      (node (ref "R8") (pin "1") (pinfunction "1_1") (pintype "passive"))
      (node (ref "U17") (pin "B8") (pinfunction "P200/NMI_B8") (pintype "bidirectional"))
    )
    (net (code "20") (name "/PWR_ON") (class "Default")
      (node (ref "U3") (pin "12") (pinfunction "~{QON}_12") (pintype "input"))
      (node (ref "U4") (pin "4") (pinfunction "~{IRQ2}_4") (pintype "output"))
    )
    (net (code "21") (name "/PWR_SEL") (class "Default")
      (node (ref "U3") (pin "2") (pinfunction "PSEL_2") (pintype "input"))
    )
    (net (code "22") (name "/RESET") (class "Default")
      (node (ref "C5") (pin "1") (pinfunction "1_1") (pintype "passive"))
      (node (ref "R9") (pin "1") (pinfunction "1_1") (pintype "passive"))
      (node (ref "U17") (pin "F8") (pinfunction "RES_F8") (pintype "passive"))
      (node (ref "U4") (pin "1") (pinfunction "~{RST}_1") (pintype "output"))
    )
    (net (code "23") (name "/RTC_BATT") (class "Default")
      (node (ref "BAT1") (pin "2") (pinfunction "2_2") (pintype "passive"))
      (node (ref "R12") (pin "2") (pinfunction "2_2") (pintype "passive"))
      (node (ref "R24") (pin "1") (pinfunction "1_1") (pintype "passive"))
    )
    (net (code "24") (name "/RTC_CS") (class "Default")
      (node (ref "U4") (pin "12") (pinfunction "~{CS}_12") (pintype "input"))
    )
    (net (code "25") (name "/RTC_IRQ") (class "Default")
      (node (ref "R23") (pin "2") (pinfunction "2_2") (pintype "passive"))
      (node (ref "U4") (pin "11") (pinfunction "~{IRQ}_11") (pintype "output"))
    )
    (net (code "26") (name "/SCL2") (class "Default")
      (node (ref "R32") (pin "1") (pinfunction "1_1") (pintype "passive"))
      (node (ref "U3") (pin "5") (pinfunction "SCL_5") (pintype "input"))
      (node (ref "U5") (pin "B1") (pinfunction "SCL_B1") (pintype "passive"))
    )
    (net (code "27") (name "/SDA2") (class "Default")
      (node (ref "R29") (pin "1") (pinfunction "1_1") (pintype "passive"))
      (node (ref "U3") (pin "6") (pinfunction "SDA_6") (pintype "bidirectional"))
      (node (ref "U5") (pin "C1") (pinfunction "SDA_C1") (pintype "passive"))
    )
    (net (code "28") (name "/SPI8_MISO") (class "Default")
      (node (ref "U4") (pin "6") (pinfunction "MISO_6") (pintype "output"))
    )
    (net (code "29") (name "/SPI8_MOSI") (class "Default")
      (node (ref "U4") (pin "9") (pinfunction "MOSI_9") (pintype "input"))
    )
    (net (code "30") (name "/SPI8_SCK") (class "Default")
      (node (ref "U4") (pin "7") (pinfunction "SCL_7") (pintype "input"))
    )
    (net (code "31") (name "/SYSV_V") (class "Default")
      (node (ref "C25") (pin "1") (pinfunction "1_1") (pintype "passive"))
      (node (ref "R19") (pin "2") (pinfunction "2_2") (pintype "passive"))
      (node (ref "R21") (pin "1") (pinfunction "1_1") (pintype "passive"))
    )
    (net (code "32") (name "/U5V_V") (class "Default")
      (node (ref "C24") (pin "1") (pinfunction "1_1") (pintype "passive"))
      (node (ref "R18") (pin "2") (pinfunction "2_2") (pintype "passive"))
      (node (ref "R20") (pin "1") (pinfunction "1_1") (pintype "passive"))
    )
    (net (code "33") (name "/USBHS_N") (class "Default")
      (node (ref "U17") (pin "F15") (pinfunction "USBHS_DM_F15") (pintype "bidirectional"))
      (node (ref "U2") (pin "5") (pinfunction "5_5") (pintype "passive"))
    )
    (net (code "34") (name "/USBHS_P") (class "Default")
      (node (ref "U17") (pin "F14") (pinfunction "USBHS_DP_F14") (pintype "bidirectional"))
      (node (ref "U2") (pin "6") (pinfunction "6_6") (pintype "passive"))
    )
    (net (code "35") (name "/USBHS_STATE") (class "Default")
      (node (ref "C8") (pin "2") (pinfunction "2_2") (pintype "passive"))
      (node (ref "R11") (pin "1") (pinfunction "1_1") (pintype "passive"))
      (node (ref "R3") (pin "2") (pinfunction "2_2") (pintype "passive"))
    )
    (net (code "36") (name "/USB_N") (class "Default")
      (node (ref "U1") (pin "5") (pinfunction "5_5") (pintype "passive"))
      (node (ref "U17") (pin "B14") (pinfunction "USB_DM_B14") (pintype "bidirectional"))
    )
    (net (code "37") (name "/USB_P") (class "Default")
      (node (ref "U1") (pin "6") (pinfunction "6_6") (pintype "passive"))
      (node (ref "U17") (pin "A14") (pinfunction "USB_DP_A14") (pintype "bidirectional"))
    )
    (net (code "38") (name "/USB_STATE") (class "Default")
      (node (ref "C4") (pin "2") (pinfunction "2_2") (pintype "passive"))
      (node (ref "R1") (pin "2") (pinfunction "2_2") (pintype "passive"))
      (node (ref "R2") (pin "1") (pinfunction "1_1") (pintype "passive"))
    )
    (net (code "39") (name "/VBUSCTRL") (class "Default")
      (node (ref "U20") (pin "C2") (pinfunction "EN_C2") (pintype "passive"))
    )
    (net (code "40") (name "/VSEL1") (class "Default")
      (node (ref "U10") (pin "A3") (pinfunction "VSEL1_A3") (pintype "passive"))
    )
    (net (code "41") (name "/VSEL2") (class "Default")
      (node (ref "U10") (pin "A2") (pinfunction "VSEL2_A2") (pintype "passive"))
    )
    (net (code "42") (name "/VSEL3") (class "Default")
      (node (ref "U10") (pin "A1") (pinfunction "VSEL3_A1") (pintype "passive"))
    )
    (net (code "43") (name "/WDT_RESET") (class "Default")
      (node (ref "U4") (pin "2") (pinfunction "WDI_2") (pintype "input"))
    )
    (net (code "44") (name "GND") (class "Default")
      (node (ref "BAT1") (pin "1") (pinfunction "1_1") (pintype "passive"))
      (node (ref "BT2") (pin "3") (pinfunction "3_3") (pintype "passive"))
      (node (ref "BT2") (pin "4") (pinfunction "4_4") (pintype "passive"))
      (node (ref "BT3") (pin "3") (pinfunction "3_3") (pintype "passive"))
      (node (ref "BT3") (pin "4") (pinfunction "4_4") (pintype "passive"))
      (node (ref "C1") (pin "1") (pinfunction "1_1") (pintype "passive"))
      (node (ref "C10") (pin "2") (pinfunction "2_2") (pintype "passive"))
      (node (ref "C103") (pin "1") (pinfunction "1_1") (pintype "passive"))
      (node (ref "C11") (pin "2") (pinfunction "2_2") (pintype "passive"))
      (node (ref "C110") (pin "2") (pinfunction "2_2") (pintype "passive"))
      (node (ref "C12") (pin "2") (pinfunction "2_2") (pintype "passive"))
      (node (ref "C13") (pin "2") (pinfunction "2_2") (pintype "passive"))
      (node (ref "C14") (pin "2") (pinfunction "2_2") (pintype "passive"))
      (node (ref "C15") (pin "2") (pinfunction "2_2") (pintype "passive"))
      (node (ref "C16") (pin "2") (pinfunction "2_2") (pintype "passive"))
      (node (ref "C17") (pin "2") (pinfunction "2_2") (pintype "passive"))
      (node (ref "C18") (pin "2") (pinfunction "2_2") (pintype "passive"))
      (node (ref "C19") (pin "2") (pinfunction "2_2") (pintype "passive"))
      (node (ref "C2") (pin "2") (pinfunction "2_2") (pintype "passive"))
      (node (ref "C20") (pin "2") (pinfunction "2_2") (pintype "passive"))
      (node (ref "C21") (pin "2") (pinfunction "2_2") (pintype "passive"))
      (node (ref "C22") (pin "2") (pinfunction "2_2") (pintype "passive"))
      (node (ref "C23") (pin "2") (pinfunction "2_2") (pintype "passive"))
      (node (ref "C24") (pin "2") (pinfunction "2_2") (pintype "passive"))
      (node (ref "C25") (pin "2") (pinfunction "2_2") (pintype "passive"))
      (node (ref "C26") (pin "2") (pinfunction "2_2") (pintype "passive"))
      (node (ref "C27") (pin "2") (pinfunction "2_2") (pintype "passive"))
      (node (ref "C28") (pin "2") (pinfunction "2_2") (pintype "passive"))
      (node (ref "C29") (pin "2") (pinfunction "2_2") (pintype "passive"))
      (node (ref "C3") (pin "1") (pinfunction "1_1") (pintype "passive"))
      (node (ref "C30") (pin "2") (pinfunction "2_2") (pintype "passive"))
      (node (ref "C31") (pin "2") (pinfunction "2_2") (pintype "passive"))
      (node (ref "C32") (pin "2") (pinfunction "2_2") (pintype "passive"))
      (node (ref "C33") (pin "2") (pinfunction "2_2") (pintype "passive"))
      (node (ref "C34") (pin "1") (pinfunction "1_1") (pintype "passive"))
      (node (ref "C4") (pin "1") (pinfunction "1_1") (pintype "passive"))
      (node (ref "C5") (pin "2") (pinfunction "2_2") (pintype "passive"))
      (node (ref "C56") (pin "2") (pinfunction "2_2") (pintype "passive"))
      (node (ref "C6") (pin "2") (pinfunction "2_2") (pintype "passive"))
      (node (ref "C60") (pin "2") (pinfunction "2_2") (pintype "passive"))
      (node (ref "C61") (pin "2") (pinfunction "2_2") (pintype "passive"))
      (node (ref "C62") (pin "2") (pinfunction "2_2") (pintype "passive"))
      (node (ref "C7") (pin "2") (pinfunction "2_2") (pintype "passive"))
      (node (ref "C73") (pin "1") (pinfunction "1_1") (pintype "passive"))
      (node (ref "C8") (pin "1") (pinfunction "1_1") (pintype "passive"))
      (node (ref "C9") (pin "2") (pinfunction "2_2") (pintype "passive"))
      (node (ref "C99") (pin "2") (pinfunction "2_2") (pintype "passive"))
      (node (ref "R10") (pin "2") (pinfunction "2_2") (pintype "passive"))
      (node (ref "R11") (pin "2") (pinfunction "2_2") (pintype "passive"))
      (node (ref "R2") (pin "2") (pinfunction "2_2") (pintype "passive"))
      (node (ref "R20") (pin "2") (pinfunction "2_2") (pintype "passive"))
      (node (ref "R21") (pin "2") (pinfunction "2_2") (pintype "passive"))
      (node (ref "R26") (pin "2") (pinfunction "2_2") (pintype "passive"))
      (node (ref "R28") (pin "1") (pinfunction "1_1") (pintype "passive"))
      (node (ref "R6") (pin "1") (pinfunction "1_1") (pintype "passive"))
      (node (ref "U1") (pin "2") (pinfunction "2_2") (pintype "passive"))
      (node (ref "U1") (pin "3") (pinfunction "3_3") (pintype "passive"))
      (node (ref "U1") (pin "4") (pinfunction "4_4") (pintype "passive"))
      (node (ref "U1") (pin "7") (pinfunction "7_7") (pintype "passive"))
      (node (ref "U10") (pin "C2") (pinfunction "GND_C2") (pintype "passive"))
      (node (ref "U17") (pin "A4") (pinfunction "VSS_A4") (pintype "power_in"))
      (node (ref "U17") (pin "A5") (pinfunction "VSS_A5") (pintype "power_in"))
      (node (ref "U17") (pin "B10") (pinfunction "VSS_B10") (pintype "power_in"))
      (node (ref "U17") (pin "B13") (pinfunction "VSS_USB_B13") (pintype "power_in"))
      (node (ref "U17") (pin "C10") (pinfunction "VSS_C10") (pintype "power_in"))
      (node (ref "U17") (pin "D2") (pinfunction "VSS_D2") (pintype "power_in"))
      (node (ref "U17") (pin "E15") (pinfunction "VSS_E15") (pintype "power_in"))
      (node (ref "U17") (pin "F12") (pinfunction "VSS1_USBHS_F12") (pintype "power_in"))
      (node (ref "U17") (pin "G12") (pinfunction "VSS2_USBHS_G12") (pintype "power_in"))
      (node (ref "U17") (pin "G14") (pinfunction "AVSS_USBHS_G14") (pintype "power_in"))
      (node (ref "U17") (pin "G15") (pinfunction "PVSS_USBHS_G15") (pintype "power_in"))
      (node (ref "U17") (pin "H2") (pinfunction "VSS_H2") (pintype "power_in"))
      (node (ref "U17") (pin "J13") (pinfunction "VSS_J13") (pintype "power_in"))
      (node (ref "U17") (pin "L11") (pinfunction "VSS_L11") (pintype "power_in"))
      (node (ref "U17") (pin "L8") (pinfunction "VSS_L8") (pintype "power_in"))
      (node (ref "U17") (pin "M1") (pinfunction "VSS_M1") (pintype "power_in"))
      (node (ref "U17") (pin "N8") (pinfunction "VREFL_N8") (pintype "power_in"))
      (node (ref "U17") (pin "N9") (pinfunction "AVSS0_N9") (pintype "power_in"))
      (node (ref "U17") (pin "P9") (pinfunction "VREFL0_P9") (pintype "bidirectional"))
      (node (ref "U17") (pin "R7") (pinfunction "VSS_R7") (pintype "power_in"))
      (node (ref "U2") (pin "2") (pinfunction "2_2") (pintype "passive"))
      (node (ref "U2") (pin "3") (pinfunction "3_3") (pintype "passive"))
      (node (ref "U2") (pin "4") (pinfunction "4_4") (pintype "passive"))
      (node (ref "U2") (pin "7") (pinfunction "7_7") (pintype "passive"))
      (node (ref "U20") (pin "C1") (pinfunction "GND_C1") (pintype "passive"))
      (node (ref "U3") (pin "17") (pinfunction "PGND_17") (pintype "power_in"))
      (node (ref "U3") (pin "18") (pinfunction "PGND_18") (pintype "power_in"))
      (node (ref "U3") (pin "25") (pinfunction "PGND_25") (pintype "power_in"))
      (node (ref "U3") (pin "9") (pinfunction "~{CE}_9") (pintype "input"))
      (node (ref "U4") (pin "17") (pinfunction "GND_17") (pintype "passive"))
      (node (ref "U5") (pin "C3") (pinfunction "GND_C3") (pintype "passive"))
      (node (ref "VD2") (pin "2") (pinfunction "2_2") (pintype "passive"))
      (node (ref "X1") (pin "2") (pinfunction "2_2") (pintype "passive"))
      (node (ref "Z1") (pin "2") (pinfunction "2_2") (pintype "passive"))
      (node (ref "Z1") (pin "4") (pinfunction "4_4") (pintype "passive"))
    )
    (net (code "45") (name "Net-(BT1-Pad3)") (class "Default")
      (node (ref "BT1") (pin "3") (pinfunction "3_3") (pintype "passive"))
      (node (ref "BT1") (pin "4") (pinfunction "4_4") (pintype "passive"))
      (node (ref "R27") (pin "2") (pinfunction "2_2") (pintype "passive"))
    )
    (net (code "46") (name "Net-(L4-Pad2)") (class "Default")
      (node (ref "L4") (pin "2") (pinfunction "2_2") (pintype "passive"))
      (node (ref "U17") (pin "A9") (pinfunction "VLO_A9") (pintype "power_in"))
      (node (ref "U17") (pin "B9") (pinfunction "VLO_B9") (pintype "power_in"))
      (node (ref "VD2") (pin "1") (pinfunction "1_1") (pintype "passive"))
    )
    (net (code "47") (name "Net-(LED1-Pad1)") (class "Default")
      (node (ref "LED1") (pin "1") (pinfunction "1_1") (pintype "passive"))
      (node (ref "R13") (pin "2") (pinfunction "2_2") (pintype "passive"))
    )
    (net (code "48") (name "Net-(LED2-Pad1)") (class "Default")
      (node (ref "LED2") (pin "1") (pinfunction "1_1") (pintype "passive"))
      (node (ref "R14") (pin "2") (pinfunction "2_2") (pintype "passive"))
    )
    (net (code "49") (name "Net-(LED3-Pad1)") (class "Default")
      (node (ref "LED3") (pin "1") (pinfunction "1_1") (pintype "passive"))
      (node (ref "R15") (pin "2") (pinfunction "2_2") (pintype "passive"))
    )
    (net (code "50") (name "Net-(U3-BTST)") (class "Default")
      (node (ref "C53") (pin "2") (pinfunction "2_2") (pintype "passive"))
      (node (ref "U3") (pin "21") (pinfunction "BTST_21") (pintype "power_in"))
    )
    (net (code "51") (name "Net-(U3-PMID)") (class "Default")
      (node (ref "C1") (pin "2") (pinfunction "2_2") (pintype "passive"))
      (node (ref "U3") (pin "23") (pinfunction "PMID_23") (pintype "output"))
    )
    (net (code "52") (name "Net-(U3-REGN)") (class "Default")
      (node (ref "C2") (pin "1") (pinfunction "1_1") (pintype "passive"))
      (node (ref "R5") (pin "2") (pinfunction "2_2") (pintype "passive"))
      (node (ref "U3") (pin "22") (pinfunction "REGN_22") (pintype "power_in"))
    )
    (net (code "53") (name "Net-(U3-TS)") (class "Default")
      (node (ref "R5") (pin "1") (pinfunction "1_1") (pintype "passive"))
      (node (ref "R6") (pin "2") (pinfunction "2_2") (pintype "passive"))
      (node (ref "U3") (pin "11") (pinfunction "TS_11") (pintype "input"))
    )
    (net (code "54") (name "Net-(U4-AF)") (class "Default")
      (node (ref "C32") (pin "1") (pinfunction "1_1") (pintype "passive"))
      (node (ref "U4") (pin "14") (pinfunction "AF_14") (pintype "output"))
    )
    (net (code "55") (name "Net-(U4-VBAT)") (class "Default")
      (node (ref "R24") (pin "2") (pinfunction "2_2") (pintype "passive"))
      (node (ref "U4") (pin "5") (pinfunction "VBAT_5") (pintype "passive"))
    )
    (net (code "56") (name "Net-(U4-XI)") (class "Default")
      (node (ref "U4") (pin "16") (pinfunction "XI_16") (pintype "passive"))
      (node (ref "Z2") (pin "2") (pinfunction "2_2") (pintype "passive"))
    )
    (net (code "57") (name "Net-(U4-XO)") (class "Default")
      (node (ref "U4") (pin "15") (pinfunction "XO_15") (pintype "passive"))
      (node (ref "Z2") (pin "1") (pinfunction "1_1") (pintype "passive"))
    )
    (net (code "58") (name "Net-(U5-REG)") (class "Default")
      (node (ref "C33") (pin "1") (pinfunction "1_1") (pintype "passive"))
      (node (ref "U5") (pin "C2") (pinfunction "REG_C2") (pintype "passive"))
    )
    (net (code "59") (name "Net-(U5-TH)") (class "Default")
      (node (ref "R26") (pin "1") (pinfunction "1_1") (pintype "passive"))
      (node (ref "U5") (pin "A1") (pinfunction "TH_A1") (pintype "passive"))
    )
    (net (code "60") (name "Net-(U10-EN)") (class "Default")
      (node (ref "R16") (pin "1") (pinfunction "1_1") (pintype "passive"))
      (node (ref "U10") (pin "B3") (pinfunction "EN_B3") (pintype "passive"))
    )
    (net (code "61") (name "Net-(U17B-P212{slash}EXTAL)") (class "Default")
      (node (ref "C6") (pin "1") (pinfunction "1_1") (pintype "passive"))
      (node (ref "U17") (pin "H15") (pinfunction "P212/EXTAL_H15") (pintype "bidirectional"))
      (node (ref "Z1") (pin "1") (pinfunction "1_1") (pintype "passive"))
    )
    (net (code "62") (name "Net-(U17B-P213{slash}XTAL)") (class "Default")
      (node (ref "C7") (pin "1") (pinfunction "1_1") (pintype "passive"))
      (node (ref "U17") (pin "H14") (pinfunction "P213/XTAL_H14") (pintype "bidirectional"))
      (node (ref "Z1") (pin "3") (pinfunction "3_3") (pintype "passive"))
    )
    (net (code "63") (name "Net-(U17B-USBHS_RREF)") (class "Default")
      (node (ref "R10") (pin "1") (pinfunction "1_1") (pintype "passive"))
      (node (ref "U17") (pin "G13") (pinfunction "USBHS_RREF_G13") (pintype "power_in"))
    )
    (net (code "64") (name "Net-(U17B-VBATT)") (class "Default")
      (node (ref "R12") (pin "1") (pinfunction "1_1") (pintype "passive"))
      (node (ref "U17") (pin "K14") (pinfunction "VBATT_K14") (pintype "power_in"))
      (node (ref "VD1") (pin "1") (pinfunction "C_1") (pintype "passive"))
    )
    (net (code "65") (name "Net-(U17B-VCL0)") (class "Default")
      (node (ref "C14") (pin "1") (pinfunction "1_1") (pintype "passive"))
      (node (ref "C15") (pin "1") (pinfunction "1_1") (pintype "passive"))
      (node (ref "C20") (pin "1") (pinfunction "1_1") (pintype "passive"))
      (node (ref "C9") (pin "1") (pinfunction "1_1") (pintype "passive"))
      (node (ref "L4") (pin "1") (pinfunction "1_1") (pintype "passive"))
      (node (ref "U17") (pin "A10") (pinfunction "VCL1_A10") (pintype "power_in"))
      (node (ref "U17") (pin "K15") (pinfunction "VCL0_K15") (pintype "bidirectional"))
      (node (ref "U17") (pin "R6") (pinfunction "VCL2_R6") (pintype "power_in"))
    )
    (net (code "66") (name "Net-(U17B-VCL_F)") (class "Default")
      (node (ref "C29") (pin "1") (pinfunction "1_1") (pintype "passive"))
      (node (ref "U17") (pin "H1") (pinfunction "VCL_F_H1") (pintype "power_in"))
    )
    (net (code "67") (name "Net-(U17B-XCIN)") (class "Default")
      (node (ref "C61") (pin "1") (pinfunction "1_1") (pintype "passive"))
      (node (ref "U17") (pin "J15") (pinfunction "XCIN_J15") (pintype "bidirectional"))
      (node (ref "Z4") (pin "1") (pinfunction "1_1") (pintype "passive"))
    )
    (net (code "68") (name "Net-(VD1-A)") (class "Default")
      (node (ref "R4") (pin "1") (pinfunction "1_1") (pintype "passive"))
      (node (ref "VD1") (pin "2") (pinfunction "A_2") (pintype "passive"))
    )
    (net (code "69") (name "unconnected-(U3-NC-Pad8)") (class "Default")
      (node (ref "U3") (pin "8") (pinfunction "NC_8") (pintype "passive"))
    )
    (net (code "70") (name "unconnected-(U3-STAT-Pad4)") (class "Default")
      (node (ref "U3") (pin "4") (pinfunction "STAT_4") (pintype "output"))
    )
    (net (code "71") (name "unconnected-(U3-~{PG}-Pad3)") (class "Default")
      (node (ref "U3") (pin "3") (pinfunction "~{PG}_3") (pintype "output"))
    )
    (net (code "72") (name "unconnected-(U4-~{EXTR}-Pad3)") (class "Default")
      (node (ref "U4") (pin "3") (pinfunction "~{EXTR}_3") (pintype "bidirectional"))
    )
    (net (code "73") (name "unconnected-(U4-~{IRQ3}-Pad8)") (class "Default")
      (node (ref "U4") (pin "8") (pinfunction "~{IRQ3}_8") (pintype "output"))
    )
    (net (code "74") (name "unconnected-(U5-ALRT-PadB2)") (class "Default")
      (node (ref "U5") (pin "B2") (pinfunction "ALRT_B2") (pintype "passive"))
    )
    (net (code "75") (name "unconnected-(U5-NC-PadA3)") (class "Default")
      (node (ref "U5") (pin "A3") (pinfunction "NC_A3") (pintype "passive"))
    )
  )
)
